# 1-Schematic_EMWAVER_UNO_V4.net
KiCad netlist of a schematic drawn in EasyEDA
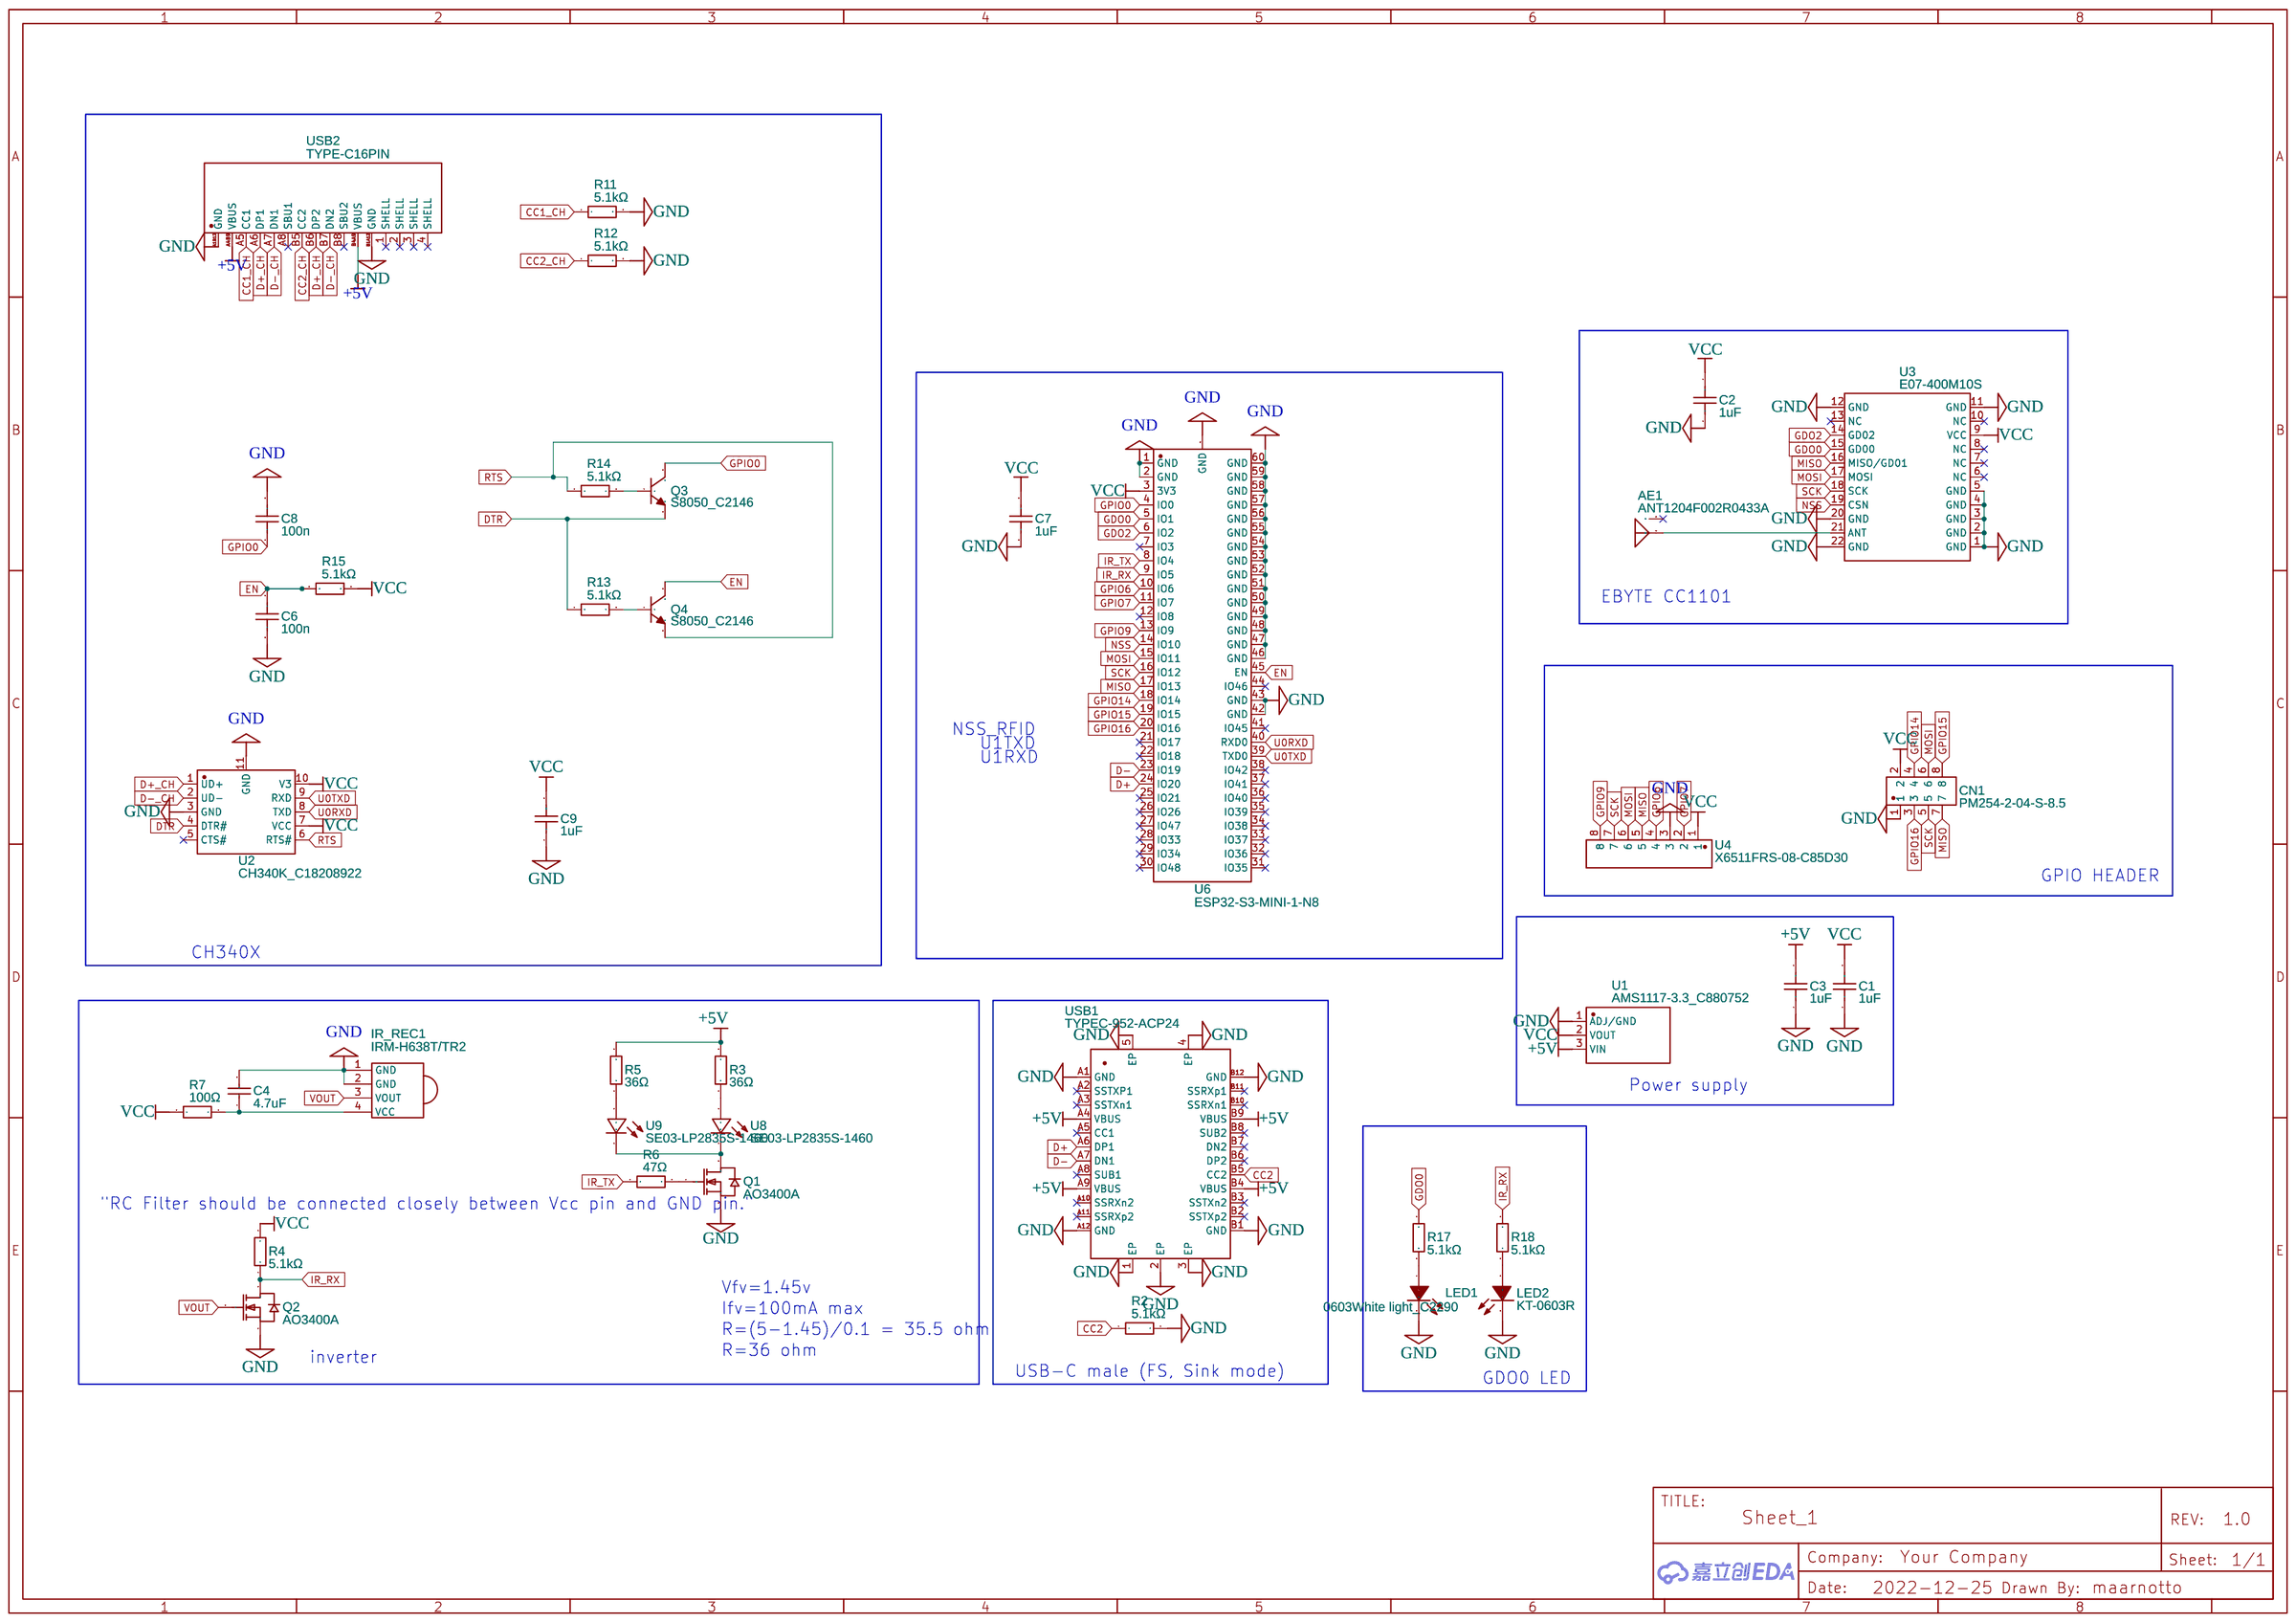
[diagram p0: schematic sheet]

(export (version "E")
  (design (tool "Eeschema 10.0.6"))
  (components
    (comp (ref "AE1")
      (value "ANT1204F002R0433A")
      (fields (field (name "Manufacturer") "YAGEO(国巨)"))
      (libsource (lib "") (part "ANT1204F002R0433A"))
    )
    (comp (ref "C1") (value "1uF") (libsource (lib "") (part "C_0603_US")))
    (comp (ref "C2") (value "1uF") (libsource (lib "") (part "C_0603_US_1")))
    (comp (ref "C3") (value "1uF") (libsource (lib "") (part "C_0603_US")))
    (comp (ref "C4")
      (value "4.7uF")
      (fields
        (field (name "Manufacturer Part") "CL10A475KO8NNNC")
        (field (name "Manufacturer") "SAMSUNG(三星)")
      )
      (libsource (lib "") (part "CL10A475KO8NNNC"))
    )
    (comp (ref "C6") (value "100n") (libsource (lib "") (part "C_0603_US_1")))
    (comp (ref "C7") (value "1uF") (libsource (lib "") (part "C_0603_US_1")))
    (comp (ref "C8") (value "100n") (libsource (lib "") (part "C_0603_US")))
    (comp (ref "C9") (value "1uF") (libsource (lib "") (part "C_0603_US")))
    (comp (ref "CN1")
      (value "PM254-2-04-S-8.5")
      (fields (field (name "Manufacturer") "HCTL(华灿天禄)"))
      (libsource (lib "") (part "PM254-2-04-S-8.5"))
    )
    (comp (ref "IR_REC1")
      (value "IRM-H638T/TR2")
      (fields (field (name "Manufacturer") "EVERLIGHT(亿光)"))
      (libsource (lib "") (part "IRM-H638T/TR2"))
    )
    (comp (ref "LED1")
      (value "0603White light_C2290")
      (fields (field (name "Manufacturer Part") "KT-0603W") (field (name "Manufacturer") "KENTO"))
      (libsource (lib "") (part "0603White light_C2290"))
    )
    (comp (ref "LED2")
      (value "KT-0603R")
      (fields (field (name "Manufacturer") "KENTO"))
      (libsource (lib "") (part "KT-0603R"))
    )
    (comp (ref "Q1")
      (value "AO3400A")
      (fields (field (name "Manufacturer") "AOS"))
      (libsource (lib "") (part "AO3400A"))
    )
    (comp (ref "Q2")
      (value "AO3400A")
      (fields (field (name "Manufacturer") "AOS"))
      (libsource (lib "") (part "AO3400A"))
    )
    (comp (ref "Q3")
      (value "S8050_C2146")
      (fields (field (name "Manufacturer Part") "S8050 J3Y") (field (name "Manufacturer") "CJ(江苏长电/长晶)"))
      (libsource (lib "") (part "S8050_C2146"))
    )
    (comp (ref "Q4")
      (value "S8050_C2146")
      (fields (field (name "Manufacturer Part") "S8050 J3Y") (field (name "Manufacturer") "CJ(江苏长电/长晶)"))
      (libsource (lib "") (part "S8050_C2146"))
    )
    (comp (ref "R2")
      (value "5.1kΩ")
      (fields
        (field (name "Manufacturer Part") "0603WAF5101T5E")
        (field (name "Manufacturer") "UNI-ROYAL(厚声)")
      )
      (libsource (lib "") (part "0603WAF5101T5E"))
    )
    (comp (ref "R3")
      (value "36Ω")
      (fields
        (field (name "Manufacturer Part") "1206W4J0360T5E")
        (field (name "Manufacturer") "UNI-ROYAL(厚声)")
      )
      (libsource (lib "") (part "1206W4J0360T5E"))
    )
    (comp (ref "R4")
      (value "5.1kΩ")
      (fields
        (field (name "Manufacturer Part") "0603WAF5101T5E")
        (field (name "Manufacturer") "UNI-ROYAL(厚声)")
      )
      (libsource (lib "") (part "0603WAF5101T5E_1"))
    )
    (comp (ref "R5")
      (value "36Ω")
      (fields
        (field (name "Manufacturer Part") "1206W4J0360T5E")
        (field (name "Manufacturer") "UNI-ROYAL(厚声)")
      )
      (libsource (lib "") (part "1206W4J0360T5E"))
    )
    (comp (ref "R6")
      (value "47Ω")
      (fields
        (field (name "Manufacturer Part") "0805W8F470JT5E")
        (field (name "Manufacturer") "UNI-ROYAL(厚声)")
      )
      (libsource (lib "") (part "0805W8F470JT5E"))
    )
    (comp (ref "R7")
      (value "100Ω")
      (fields
        (field (name "Manufacturer Part") "0805W8F1000T5E")
        (field (name "Manufacturer") "UNI-ROYAL(厚声)")
      )
      (libsource (lib "") (part "0805W8F1000T5E"))
    )
    (comp (ref "R11")
      (value "5.1kΩ")
      (fields
        (field (name "Manufacturer Part") "0603WAF5101T5E")
        (field (name "Manufacturer") "UNI-ROYAL(厚声)")
      )
      (libsource (lib "") (part "0603WAF5101T5E"))
    )
    (comp (ref "R12")
      (value "5.1kΩ")
      (fields
        (field (name "Manufacturer Part") "0603WAF5101T5E")
        (field (name "Manufacturer") "UNI-ROYAL(厚声)")
      )
      (libsource (lib "") (part "0603WAF5101T5E"))
    )
    (comp (ref "R13")
      (value "5.1kΩ")
      (fields
        (field (name "Manufacturer Part") "0603WAF5101T5E")
        (field (name "Manufacturer") "UNI-ROYAL(厚声)")
      )
      (libsource (lib "") (part "0603WAF5101T5E"))
    )
    (comp (ref "R14")
      (value "5.1kΩ")
      (fields
        (field (name "Manufacturer Part") "0603WAF5101T5E")
        (field (name "Manufacturer") "UNI-ROYAL(厚声)")
      )
      (libsource (lib "") (part "0603WAF5101T5E"))
    )
    (comp (ref "R15")
      (value "5.1kΩ")
      (fields
        (field (name "Manufacturer Part") "0603WAF5101T5E")
        (field (name "Manufacturer") "UNI-ROYAL(厚声)")
      )
      (libsource (lib "") (part "0603WAF5101T5E"))
    )
    (comp (ref "R17")
      (value "5.1kΩ")
      (fields
        (field (name "Manufacturer Part") "0603WAF5101T5E")
        (field (name "Manufacturer") "UNI-ROYAL(厚声)")
      )
      (libsource (lib "") (part "0603WAF5101T5E_1"))
    )
    (comp (ref "R18")
      (value "5.1kΩ")
      (fields
        (field (name "Manufacturer Part") "0603WAF5101T5E")
        (field (name "Manufacturer") "UNI-ROYAL(厚声)")
      )
      (libsource (lib "") (part "0603WAF5101T5E_1"))
    )
    (comp (ref "U1")
      (value "AMS1117-3.3_C880752")
      (fields (field (name "Manufacturer Part") "AMS1117-3.3") (field (name "Manufacturer") "Slkor(萨科微)"))
      (libsource (lib "") (part "AMS1117-3.3_C880752"))
    )
    (comp (ref "U2")
      (value "CH340K_C18208922")
      (fields (field (name "Manufacturer Part") "CH340K") (field (name "Manufacturer") "WCH(南京沁恒)"))
      (libsource (lib "") (part "CH340K_C18208922"))
    )
    (comp (ref "U3")
      (value "E07-400M10S")
      (fields (field (name "Manufacturer") "EBYTE(亿佰特)"))
      (libsource (lib "") (part "E07-400M10S"))
    )
    (comp (ref "U4")
      (value "X6511FRS-08-C85D30")
      (fields (field (name "Manufacturer") "XKB Connectivity(中国星坤)"))
      (libsource (lib "") (part "X6511FRS-08-C85D30"))
    )
    (comp (ref "U6")
      (value "ESP32-S3-MINI-1-N8")
      (fields (field (name "Manufacturer") "ESPRESSIF(乐鑫)"))
      (libsource (lib "") (part "ESP32-S3-MINI-1-N8"))
    )
    (comp (ref "U8")
      (value "SE03-LP2835S-1460")
      (fields (field (name "Manufacturer") "XSSY(旭晟)"))
      (libsource (lib "") (part "SE03-LP2835S-1460"))
    )
    (comp (ref "U9")
      (value "SE03-LP2835S-1460")
      (fields (field (name "Manufacturer") "XSSY(旭晟)"))
      (libsource (lib "") (part "SE03-LP2835S-1460"))
    )
    (comp (ref "USB1")
      (value "TYPEC-952-ACP24")
      (fields (field (name "Manufacturer") "XUNPU(讯普)"))
      (libsource (lib "") (part "TYPEC-952-ACP24"))
    )
    (comp (ref "USB2")
      (value "TYPE-C16PIN")
      (fields (field (name "Manufacturer") "SHOU HAN(首韩)"))
      (libsource (lib "") (part "TYPE-C16PIN"))
    )
  )
  (nets
    (net (code "1") (name "+5V") (class "Default")
      (node (ref "C3") (pin "2") (pinfunction "2_2") (pintype "unspecified"))
      (node (ref "R3") (pin "2") (pinfunction "2_2") (pintype "input"))
      (node (ref "R5") (pin "2") (pinfunction "2_2") (pintype "input"))
      (node (ref "U1") (pin "3") (pinfunction "VIN_3") (pintype "unspecified"))
      (node (ref "USB1") (pin "A4") (pinfunction "VBUS_A4") (pintype "unspecified"))
      (node (ref "USB1") (pin "A9") (pinfunction "VBUS_A9") (pintype "unspecified"))
      (node (ref "USB1") (pin "B4") (pinfunction "VBUS_B4") (pintype "unspecified"))
      (node (ref "USB1") (pin "B9") (pinfunction "VBUS_B9") (pintype "unspecified"))
      (node (ref "USB2") (pin "A4B9") (pinfunction "VBUS_A4B9") (pintype "unspecified"))
      (node (ref "USB2") (pin "B4A9") (pinfunction "VBUS_B4A9") (pintype "unspecified"))
    )
    (net (code "2") (name "CC1_CH") (class "Default")
      (node (ref "R11") (pin "1") (pinfunction "1_1") (pintype "input"))
      (node (ref "USB2") (pin "A5") (pinfunction "CC1_A5") (pintype "unspecified"))
    )
    (net (code "3") (name "CC2") (class "Default")
      (node (ref "R2") (pin "1") (pinfunction "1_1") (pintype "input"))
      (node (ref "USB1") (pin "B5") (pinfunction "CC2_B5") (pintype "unspecified"))
    )
    (net (code "4") (name "CC2_CH") (class "Default")
      (node (ref "R12") (pin "1") (pinfunction "1_1") (pintype "input"))
      (node (ref "USB2") (pin "B5") (pinfunction "CC2_B5") (pintype "unspecified"))
    )
    (net (code "5") (name "D+") (class "Default")
      (node (ref "U6") (pin "24") (pinfunction "IO20_24") (pintype "unspecified"))
      (node (ref "USB1") (pin "A6") (pinfunction "DP1_A6") (pintype "unspecified"))
    )
    (net (code "6") (name "D+_CH") (class "Default")
      (node (ref "U2") (pin "1") (pinfunction "UD+_1") (pintype "unspecified"))
      (node (ref "USB2") (pin "A6") (pinfunction "DP1_A6") (pintype "unspecified"))
      (node (ref "USB2") (pin "B6") (pinfunction "DP2_B6") (pintype "unspecified"))
    )
    (net (code "7") (name "D-") (class "Default")
      (node (ref "U6") (pin "23") (pinfunction "IO19_23") (pintype "unspecified"))
      (node (ref "USB1") (pin "A7") (pinfunction "DN1_A7") (pintype "unspecified"))
    )
    (net (code "8") (name "D-_CH") (class "Default")
      (node (ref "U2") (pin "2") (pinfunction "UD-_2") (pintype "unspecified"))
      (node (ref "USB2") (pin "A7") (pinfunction "DN1_A7") (pintype "unspecified"))
      (node (ref "USB2") (pin "B7") (pinfunction "DN2_B7") (pintype "unspecified"))
    )
    (net (code "9") (name "DTR") (class "Default")
      (node (ref "Q3") (pin "2") (pinfunction "E_2") (pintype "unspecified"))
      (node (ref "R13") (pin "1") (pinfunction "1_1") (pintype "input"))
      (node (ref "U2") (pin "4") (pinfunction "DTR#_4") (pintype "unspecified"))
    )
    (net (code "10") (name "EN") (class "Default")
      (node (ref "C6") (pin "1") (pinfunction "1_1") (pintype "unspecified"))
      (node (ref "Q4") (pin "3") (pinfunction "C_3") (pintype "unspecified"))
      (node (ref "R15") (pin "1") (pinfunction "1_1") (pintype "input"))
      (node (ref "U6") (pin "45") (pinfunction "EN_45") (pintype "unspecified"))
    )
    (net (code "11") (name "GDO0") (class "Default")
      (node (ref "R17") (pin "2") (pinfunction "2_2") (pintype "input"))
      (node (ref "U3") (pin "15") (pinfunction "GD00_15") (pintype "unspecified"))
      (node (ref "U6") (pin "5") (pinfunction "IO1_5") (pintype "unspecified"))
    )
    (net (code "12") (name "GDO2") (class "Default")
      (node (ref "U3") (pin "14") (pinfunction "GD02_14") (pintype "unspecified"))
      (node (ref "U6") (pin "6") (pinfunction "IO2_6") (pintype "unspecified"))
    )
    (net (code "13") (name "GND") (class "Default")
      (node (ref "C1") (pin "1") (pinfunction "1_1") (pintype "unspecified"))
      (node (ref "C2") (pin "2") (pinfunction "2_2") (pintype "unspecified"))
      (node (ref "C3") (pin "1") (pinfunction "1_1") (pintype "unspecified"))
      (node (ref "C4") (pin "2") (pinfunction "2_2") (pintype "input"))
      (node (ref "C6") (pin "2") (pinfunction "2_2") (pintype "unspecified"))
      (node (ref "C7") (pin "2") (pinfunction "2_2") (pintype "unspecified"))
      (node (ref "C8") (pin "2") (pinfunction "2_2") (pintype "unspecified"))
      (node (ref "C9") (pin "1") (pinfunction "1_1") (pintype "unspecified"))
      (node (ref "CN1") (pin "1") (pinfunction "1_1") (pintype "unspecified"))
      (node (ref "IR_REC1") (pin "1") (pinfunction "GND_1") (pintype "input"))
      (node (ref "IR_REC1") (pin "2") (pinfunction "GND_2") (pintype "input"))
      (node (ref "LED1") (pin "2") (pinfunction "K_2") (pintype "unspecified"))
      (node (ref "LED2") (pin "1") (pinfunction "K_1") (pintype "unspecified"))
      (node (ref "Q1") (pin "2") (pinfunction "S_2") (pintype "unspecified"))
      (node (ref "Q2") (pin "2") (pinfunction "S_2") (pintype "unspecified"))
      (node (ref "R11") (pin "2") (pinfunction "2_2") (pintype "input"))
      (node (ref "R12") (pin "2") (pinfunction "2_2") (pintype "input"))
      (node (ref "R2") (pin "2") (pinfunction "2_2") (pintype "input"))
      (node (ref "U1") (pin "1") (pinfunction "ADJ/GND_1") (pintype "unspecified"))
      (node (ref "U2") (pin "11") (pinfunction "GND_11") (pintype "unspecified"))
      (node (ref "U2") (pin "3") (pinfunction "GND_3") (pintype "unspecified"))
      (node (ref "U3") (pin "1") (pinfunction "GND_1") (pintype "unspecified"))
      (node (ref "U3") (pin "11") (pinfunction "GND_11") (pintype "unspecified"))
      (node (ref "U3") (pin "12") (pinfunction "GND_12") (pintype "unspecified"))
      (node (ref "U3") (pin "2") (pinfunction "GND_2") (pintype "unspecified"))
      (node (ref "U3") (pin "20") (pinfunction "GND_20") (pintype "unspecified"))
      (node (ref "U3") (pin "22") (pinfunction "GND_22") (pintype "unspecified"))
      (node (ref "U3") (pin "3") (pinfunction "GND_3") (pintype "unspecified"))
      (node (ref "U3") (pin "4") (pinfunction "GND_4") (pintype "unspecified"))
      (node (ref "U3") (pin "5") (pinfunction "GND_5") (pintype "unspecified"))
      (node (ref "U4") (pin "3") (pinfunction "3_3") (pintype "unspecified"))
      (node (ref "U6") (pin "1") (pinfunction "GND_1") (pintype "unspecified"))
      (node (ref "U6") (pin "2") (pinfunction "GND_2") (pintype "unspecified"))
      (node (ref "U6") (pin "42") (pinfunction "GND_42") (pintype "unspecified"))
      (node (ref "U6") (pin "43") (pinfunction "GND_43") (pintype "unspecified"))
      (node (ref "U6") (pin "46") (pinfunction "GND_46") (pintype "unspecified"))
      (node (ref "U6") (pin "47") (pinfunction "GND_47") (pintype "unspecified"))
      (node (ref "U6") (pin "48") (pinfunction "GND_48") (pintype "unspecified"))
      (node (ref "U6") (pin "49") (pinfunction "GND_49") (pintype "unspecified"))
      (node (ref "U6") (pin "50") (pinfunction "GND_50") (pintype "unspecified"))
      (node (ref "U6") (pin "51") (pinfunction "GND_51") (pintype "unspecified"))
      (node (ref "U6") (pin "52") (pinfunction "GND_52") (pintype "unspecified"))
      (node (ref "U6") (pin "53") (pinfunction "GND_53") (pintype "unspecified"))
      (node (ref "U6") (pin "54") (pinfunction "GND_54") (pintype "unspecified"))
      (node (ref "U6") (pin "55") (pinfunction "GND_55") (pintype "unspecified"))
      (node (ref "U6") (pin "56") (pinfunction "GND_56") (pintype "unspecified"))
      (node (ref "U6") (pin "57") (pinfunction "GND_57") (pintype "unspecified"))
      (node (ref "U6") (pin "58") (pinfunction "GND_58") (pintype "unspecified"))
      (node (ref "U6") (pin "59") (pinfunction "GND_59") (pintype "unspecified"))
      (node (ref "U6") (pin "60") (pinfunction "GND_60") (pintype "unspecified"))
      (node (ref "U6") (pin "GND") (pinfunction "GND_GND") (pintype "unspecified"))
      (node (ref "USB1") (pin "1") (pinfunction "EP_1") (pintype "unspecified"))
      (node (ref "USB1") (pin "2") (pinfunction "EP_2") (pintype "unspecified"))
      (node (ref "USB1") (pin "3") (pinfunction "EP_3") (pintype "unspecified"))
      (node (ref "USB1") (pin "4") (pinfunction "EP_4") (pintype "unspecified"))
      (node (ref "USB1") (pin "5") (pinfunction "EP_5") (pintype "unspecified"))
      (node (ref "USB1") (pin "A1") (pinfunction "GND_A1") (pintype "unspecified"))
      (node (ref "USB1") (pin "A12") (pinfunction "GND_A12") (pintype "unspecified"))
      (node (ref "USB1") (pin "B1") (pinfunction "GND_B1") (pintype "unspecified"))
      (node (ref "USB1") (pin "B12") (pinfunction "GND_B12") (pintype "unspecified"))
      (node (ref "USB2") (pin "A1B12") (pinfunction "GND_A1B12") (pintype "unspecified"))
      (node (ref "USB2") (pin "B1A12") (pinfunction "GND_B1A12") (pintype "unspecified"))
    )
    (net (code "14") (name "GPIO0") (class "Default")
      (node (ref "C8") (pin "1") (pinfunction "1_1") (pintype "unspecified"))
      (node (ref "Q3") (pin "3") (pinfunction "C_3") (pintype "unspecified"))
      (node (ref "U6") (pin "4") (pinfunction "IO0_4") (pintype "unspecified"))
    )
    (net (code "15") (name "GPIO6") (class "Default")
      (node (ref "U4") (pin "4") (pinfunction "4_4") (pintype "unspecified"))
      (node (ref "U6") (pin "10") (pinfunction "IO6_10") (pintype "unspecified"))
    )
    (net (code "16") (name "GPIO7") (class "Default")
      (node (ref "U4") (pin "2") (pinfunction "2_2") (pintype "unspecified"))
      (node (ref "U6") (pin "11") (pinfunction "IO7_11") (pintype "unspecified"))
    )
    (net (code "17") (name "GPIO9") (class "Default")
      (node (ref "U4") (pin "8") (pinfunction "8_8") (pintype "unspecified"))
      (node (ref "U6") (pin "13") (pinfunction "IO9_13") (pintype "unspecified"))
    )
    (net (code "18") (name "GPIO14") (class "Default")
      (node (ref "CN1") (pin "4") (pinfunction "4_4") (pintype "unspecified"))
      (node (ref "U6") (pin "18") (pinfunction "IO14_18") (pintype "unspecified"))
    )
    (net (code "19") (name "GPIO15") (class "Default")
      (node (ref "CN1") (pin "8") (pinfunction "8_8") (pintype "unspecified"))
      (node (ref "U6") (pin "19") (pinfunction "IO15_19") (pintype "unspecified"))
    )
    (net (code "20") (name "GPIO16") (class "Default")
      (node (ref "CN1") (pin "3") (pinfunction "3_3") (pintype "unspecified"))
      (node (ref "U6") (pin "20") (pinfunction "IO16_20") (pintype "unspecified"))
    )
    (net (code "21") (name "IR_RX") (class "Default")
      (node (ref "Q2") (pin "3") (pinfunction "D_3") (pintype "unspecified"))
      (node (ref "R18") (pin "2") (pinfunction "2_2") (pintype "input"))
      (node (ref "R4") (pin "1") (pinfunction "1_1") (pintype "input"))
      (node (ref "U6") (pin "9") (pinfunction "IO5_9") (pintype "unspecified"))
    )
    (net (code "22") (name "IR_TX") (class "Default")
      (node (ref "R6") (pin "1") (pinfunction "1_1") (pintype "input"))
      (node (ref "U6") (pin "8") (pinfunction "IO4_8") (pintype "unspecified"))
    )
    (net (code "23") (name "MISO") (class "Default")
      (node (ref "CN1") (pin "7") (pinfunction "7_7") (pintype "unspecified"))
      (node (ref "U3") (pin "16") (pinfunction "MISO/GD01_16") (pintype "unspecified"))
      (node (ref "U4") (pin "5") (pinfunction "5_5") (pintype "unspecified"))
      (node (ref "U6") (pin "17") (pinfunction "IO13_17") (pintype "unspecified"))
    )
    (net (code "24") (name "MOSI") (class "Default")
      (node (ref "CN1") (pin "6") (pinfunction "6_6") (pintype "unspecified"))
      (node (ref "U3") (pin "17") (pinfunction "MOSI_17") (pintype "unspecified"))
      (node (ref "U4") (pin "6") (pinfunction "6_6") (pintype "unspecified"))
      (node (ref "U6") (pin "15") (pinfunction "IO11_15") (pintype "unspecified"))
    )
    (net (code "25") (name "NSS") (class "Default")
      (node (ref "U3") (pin "19") (pinfunction "CSN_19") (pintype "unspecified"))
      (node (ref "U6") (pin "14") (pinfunction "IO10_14") (pintype "unspecified"))
    )
    (net (code "26") (name "Net-(IR_REC1-VCC)") (class "Default")
      (node (ref "C4") (pin "1") (pinfunction "1_1") (pintype "input"))
      (node (ref "IR_REC1") (pin "4") (pinfunction "VCC_4") (pintype "input"))
      (node (ref "R7") (pin "2") (pinfunction "2_2") (pintype "input"))
    )
    (net (code "27") (name "Net-(LED1-A)") (class "Default")
      (node (ref "LED1") (pin "1") (pinfunction "A_1") (pintype "unspecified"))
      (node (ref "R17") (pin "1") (pinfunction "1_1") (pintype "input"))
    )
    (net (code "28") (name "Net-(LED2-A)") (class "Default")
      (node (ref "LED2") (pin "2") (pinfunction "A_2") (pintype "unspecified"))
      (node (ref "R18") (pin "1") (pinfunction "1_1") (pintype "input"))
    )
    (net (code "29") (name "Net-(Q1-D)") (class "Default")
      (node (ref "Q1") (pin "3") (pinfunction "D_3") (pintype "unspecified"))
      (node (ref "U8") (pin "2") (pinfunction "C_2") (pintype "unspecified"))
      (node (ref "U9") (pin "2") (pinfunction "C_2") (pintype "unspecified"))
    )
    (net (code "30") (name "Net-(Q1-G)") (class "Default")
      (node (ref "Q1") (pin "1") (pinfunction "G_1") (pintype "unspecified"))
      (node (ref "R6") (pin "2") (pinfunction "2_2") (pintype "input"))
    )
    (net (code "31") (name "Net-(Q3-B)") (class "Default")
      (node (ref "Q3") (pin "1") (pinfunction "B_1") (pintype "unspecified"))
      (node (ref "R14") (pin "2") (pinfunction "2_2") (pintype "input"))
    )
    (net (code "32") (name "Net-(Q4-B)") (class "Default")
      (node (ref "Q4") (pin "1") (pinfunction "B_1") (pintype "unspecified"))
      (node (ref "R13") (pin "2") (pinfunction "2_2") (pintype "input"))
    )
    (net (code "33") (name "Net-(U3-ANT)") (class "Default")
      (node (ref "AE1") (pin "S1") (pinfunction "S1_S1") (pintype "unspecified"))
      (node (ref "U3") (pin "21") (pinfunction "ANT_21") (pintype "unspecified"))
    )
    (net (code "34") (name "Net-(U8-A)") (class "Default")
      (node (ref "R3") (pin "1") (pinfunction "1_1") (pintype "input"))
      (node (ref "U8") (pin "1") (pinfunction "A_1") (pintype "unspecified"))
    )
    (net (code "35") (name "Net-(U9-A)") (class "Default")
      (node (ref "R5") (pin "1") (pinfunction "1_1") (pintype "input"))
      (node (ref "U9") (pin "1") (pinfunction "A_1") (pintype "unspecified"))
    )
    (net (code "36") (name "RTS") (class "Default")
      (node (ref "Q4") (pin "2") (pinfunction "E_2") (pintype "unspecified"))
      (node (ref "R14") (pin "1") (pinfunction "1_1") (pintype "input"))
      (node (ref "U2") (pin "6") (pinfunction "RTS#_6") (pintype "unspecified"))
    )
    (net (code "37") (name "SCK") (class "Default")
      (node (ref "CN1") (pin "5") (pinfunction "5_5") (pintype "unspecified"))
      (node (ref "U3") (pin "18") (pinfunction "SCK_18") (pintype "unspecified"))
      (node (ref "U4") (pin "7") (pinfunction "7_7") (pintype "unspecified"))
      (node (ref "U6") (pin "16") (pinfunction "IO12_16") (pintype "unspecified"))
    )
    (net (code "38") (name "U0RXD") (class "Default")
      (node (ref "U2") (pin "8") (pinfunction "TXD_8") (pintype "unspecified"))
      (node (ref "U6") (pin "40") (pinfunction "RXD0_40") (pintype "unspecified"))
    )
    (net (code "39") (name "U0TXD") (class "Default")
      (node (ref "U2") (pin "9") (pinfunction "RXD_9") (pintype "unspecified"))
      (node (ref "U6") (pin "39") (pinfunction "TXD0_39") (pintype "unspecified"))
    )
    (net (code "40") (name "VCC") (class "Default")
      (node (ref "C1") (pin "2") (pinfunction "2_2") (pintype "unspecified"))
      (node (ref "C2") (pin "1") (pinfunction "1_1") (pintype "unspecified"))
      (node (ref "C7") (pin "1") (pinfunction "1_1") (pintype "unspecified"))
      (node (ref "C9") (pin "2") (pinfunction "2_2") (pintype "unspecified"))
      (node (ref "CN1") (pin "2") (pinfunction "2_2") (pintype "unspecified"))
      (node (ref "R15") (pin "2") (pinfunction "2_2") (pintype "input"))
      (node (ref "R4") (pin "2") (pinfunction "2_2") (pintype "input"))
      (node (ref "R7") (pin "1") (pinfunction "1_1") (pintype "input"))
      (node (ref "U1") (pin "2") (pinfunction "VOUT_2") (pintype "unspecified"))
      (node (ref "U2") (pin "10") (pinfunction "V3_10") (pintype "unspecified"))
      (node (ref "U2") (pin "7") (pinfunction "VCC_7") (pintype "unspecified"))
      (node (ref "U3") (pin "9") (pinfunction "VCC_9") (pintype "unspecified"))
      (node (ref "U4") (pin "1") (pinfunction "1_1") (pintype "unspecified"))
      (node (ref "U6") (pin "3") (pinfunction "3V3_3") (pintype "unspecified"))
    )
    (net (code "41") (name "VOUT") (class "Default")
      (node (ref "IR_REC1") (pin "3") (pinfunction "VOUT_3") (pintype "input"))
      (node (ref "Q2") (pin "1") (pinfunction "G_1") (pintype "unspecified"))
    )
    (net (code "42") (name "unconnected-(AE1-PadS2)") (class "Default")
      (node (ref "AE1") (pin "S2") (pinfunction "S2_S2") (pintype "unspecified+no_connect"))
    )
    (net (code "43") (name "unconnected-(U2-CTS#-Pad5)") (class "Default")
      (node (ref "U2") (pin "5") (pinfunction "CTS#_5") (pintype "unspecified+no_connect"))
    )
    (net (code "44") (name "unconnected-(U3-NC-Pad6)") (class "Default")
      (node (ref "U3") (pin "6") (pinfunction "NC_6") (pintype "unspecified+no_connect"))
    )
    (net (code "45") (name "unconnected-(U3-NC-Pad7)") (class "Default")
      (node (ref "U3") (pin "7") (pinfunction "NC_7") (pintype "unspecified+no_connect"))
    )
    (net (code "46") (name "unconnected-(U3-NC-Pad8)") (class "Default")
      (node (ref "U3") (pin "8") (pinfunction "NC_8") (pintype "unspecified+no_connect"))
    )
    (net (code "47") (name "unconnected-(U3-NC-Pad10)") (class "Default")
      (node (ref "U3") (pin "10") (pinfunction "NC_10") (pintype "unspecified+no_connect"))
    )
    (net (code "48") (name "unconnected-(U3-NC-Pad13)") (class "Default")
      (node (ref "U3") (pin "13") (pinfunction "NC_13") (pintype "unspecified+no_connect"))
    )
    (net (code "49") (name "unconnected-(U6-IO3-Pad7)") (class "Default")
      (node (ref "U6") (pin "7") (pinfunction "IO3_7") (pintype "unspecified+no_connect"))
    )
    (net (code "50") (name "unconnected-(U6-IO8-Pad12)") (class "Default")
      (node (ref "U6") (pin "12") (pinfunction "IO8_12") (pintype "unspecified+no_connect"))
    )
    (net (code "51") (name "unconnected-(U6-IO17-Pad21)") (class "Default")
      (node (ref "U6") (pin "21") (pinfunction "IO17_21") (pintype "unspecified+no_connect"))
    )
    (net (code "52") (name "unconnected-(U6-IO18-Pad22)") (class "Default")
      (node (ref "U6") (pin "22") (pinfunction "IO18_22") (pintype "unspecified+no_connect"))
    )
    (net (code "53") (name "unconnected-(U6-IO21-Pad25)") (class "Default")
      (node (ref "U6") (pin "25") (pinfunction "IO21_25") (pintype "unspecified+no_connect"))
    )
    (net (code "54") (name "unconnected-(U6-IO26-Pad26)") (class "Default")
      (node (ref "U6") (pin "26") (pinfunction "IO26_26") (pintype "unspecified+no_connect"))
    )
    (net (code "55") (name "unconnected-(U6-IO33-Pad28)") (class "Default")
      (node (ref "U6") (pin "28") (pinfunction "IO33_28") (pintype "unspecified+no_connect"))
    )
    (net (code "56") (name "unconnected-(U6-IO34-Pad29)") (class "Default")
      (node (ref "U6") (pin "29") (pinfunction "IO34_29") (pintype "unspecified+no_connect"))
    )
    (net (code "57") (name "unconnected-(U6-IO35-Pad31)") (class "Default")
      (node (ref "U6") (pin "31") (pinfunction "IO35_31") (pintype "unspecified+no_connect"))
    )
    (net (code "58") (name "unconnected-(U6-IO36-Pad32)") (class "Default")
      (node (ref "U6") (pin "32") (pinfunction "IO36_32") (pintype "unspecified+no_connect"))
    )
    (net (code "59") (name "unconnected-(U6-IO37-Pad33)") (class "Default")
      (node (ref "U6") (pin "33") (pinfunction "IO37_33") (pintype "unspecified+no_connect"))
    )
    (net (code "60") (name "unconnected-(U6-IO38-Pad34)") (class "Default")
      (node (ref "U6") (pin "34") (pinfunction "IO38_34") (pintype "unspecified+no_connect"))
    )
    (net (code "61") (name "unconnected-(U6-IO39-Pad35)") (class "Default")
      (node (ref "U6") (pin "35") (pinfunction "IO39_35") (pintype "unspecified+no_connect"))
    )
    (net (code "62") (name "unconnected-(U6-IO40-Pad36)") (class "Default")
      (node (ref "U6") (pin "36") (pinfunction "IO40_36") (pintype "unspecified+no_connect"))
    )
    (net (code "63") (name "unconnected-(U6-IO41-Pad37)") (class "Default")
      (node (ref "U6") (pin "37") (pinfunction "IO41_37") (pintype "unspecified+no_connect"))
    )
    (net (code "64") (name "unconnected-(U6-IO42-Pad38)") (class "Default")
      (node (ref "U6") (pin "38") (pinfunction "IO42_38") (pintype "unspecified+no_connect"))
    )
    (net (code "65") (name "unconnected-(U6-IO45-Pad41)") (class "Default")
      (node (ref "U6") (pin "41") (pinfunction "IO45_41") (pintype "unspecified+no_connect"))
    )
    (net (code "66") (name "unconnected-(U6-IO46-Pad44)") (class "Default")
      (node (ref "U6") (pin "44") (pinfunction "IO46_44") (pintype "unspecified+no_connect"))
    )
    (net (code "67") (name "unconnected-(U6-IO47-Pad27)") (class "Default")
      (node (ref "U6") (pin "27") (pinfunction "IO47_27") (pintype "unspecified+no_connect"))
    )
    (net (code "68") (name "unconnected-(U6-IO48-Pad30)") (class "Default")
      (node (ref "U6") (pin "30") (pinfunction "IO48_30") (pintype "unspecified+no_connect"))
    )
    (net (code "69") (name "unconnected-(USB1-CC1-PadA5)") (class "Default")
      (node (ref "USB1") (pin "A5") (pinfunction "CC1_A5") (pintype "unspecified+no_connect"))
    )
    (net (code "70") (name "unconnected-(USB1-DN2-PadB7)") (class "Default")
      (node (ref "USB1") (pin "B7") (pinfunction "DN2_B7") (pintype "unspecified+no_connect"))
    )
    (net (code "71") (name "unconnected-(USB1-DP2-PadB6)") (class "Default")
      (node (ref "USB1") (pin "B6") (pinfunction "DP2_B6") (pintype "unspecified+no_connect"))
    )
    (net (code "72") (name "unconnected-(USB1-SSRXn1-PadB10)") (class "Default")
      (node (ref "USB1") (pin "B10") (pinfunction "SSRXn1_B10") (pintype "unspecified+no_connect"))
    )
    (net (code "73") (name "unconnected-(USB1-SSRXn2-PadA10)") (class "Default")
      (node (ref "USB1") (pin "A10") (pinfunction "SSRXn2_A10") (pintype "unspecified+no_connect"))
    )
    (net (code "74") (name "unconnected-(USB1-SSRXp1-PadB11)") (class "Default")
      (node (ref "USB1") (pin "B11") (pinfunction "SSRXp1_B11") (pintype "unspecified+no_connect"))
    )
    (net (code "75") (name "unconnected-(USB1-SSRXp2-PadA11)") (class "Default")
      (node (ref "USB1") (pin "A11") (pinfunction "SSRXp2_A11") (pintype "unspecified+no_connect"))
    )
    (net (code "76") (name "unconnected-(USB1-SSTXP1-PadA2)") (class "Default")
      (node (ref "USB1") (pin "A2") (pinfunction "SSTXP1_A2") (pintype "unspecified+no_connect"))
    )
    (net (code "77") (name "unconnected-(USB1-SSTXn1-PadA3)") (class "Default")
      (node (ref "USB1") (pin "A3") (pinfunction "SSTXn1_A3") (pintype "unspecified+no_connect"))
    )
    (net (code "78") (name "unconnected-(USB1-SSTXn2-PadB3)") (class "Default")
      (node (ref "USB1") (pin "B3") (pinfunction "SSTXn2_B3") (pintype "unspecified+no_connect"))
    )
    (net (code "79") (name "unconnected-(USB1-SSTXp2-PadB2)") (class "Default")
      (node (ref "USB1") (pin "B2") (pinfunction "SSTXp2_B2") (pintype "unspecified+no_connect"))
    )
    (net (code "80") (name "unconnected-(USB1-SUB1-PadA8)") (class "Default")
      (node (ref "USB1") (pin "A8") (pinfunction "SUB1_A8") (pintype "unspecified+no_connect"))
    )
    (net (code "81") (name "unconnected-(USB1-SUB2-PadB8)") (class "Default")
      (node (ref "USB1") (pin "B8") (pinfunction "SUB2_B8") (pintype "unspecified+no_connect"))
    )
    (net (code "82") (name "unconnected-(USB2-SBU1-PadA8)") (class "Default")
      (node (ref "USB2") (pin "A8") (pinfunction "SBU1_A8") (pintype "unspecified+no_connect"))
    )
    (net (code "83") (name "unconnected-(USB2-SBU2-PadB8)") (class "Default")
      (node (ref "USB2") (pin "B8") (pinfunction "SBU2_B8") (pintype "unspecified+no_connect"))
    )
    (net (code "84") (name "unconnected-(USB2-SHELL-Pad1)") (class "Default")
      (node (ref "USB2") (pin "1") (pinfunction "SHELL_1") (pintype "unspecified+no_connect"))
    )
    (net (code "85") (name "unconnected-(USB2-SHELL-Pad2)") (class "Default")
      (node (ref "USB2") (pin "2") (pinfunction "SHELL_2") (pintype "unspecified+no_connect"))
    )
    (net (code "86") (name "unconnected-(USB2-SHELL-Pad3)") (class "Default")
      (node (ref "USB2") (pin "3") (pinfunction "SHELL_3") (pintype "unspecified+no_connect"))
    )
    (net (code "87") (name "unconnected-(USB2-SHELL-Pad4)") (class "Default")
      (node (ref "USB2") (pin "4") (pinfunction "SHELL_4") (pintype "unspecified+no_connect"))
    )
  )
)
